# MiniBox.net
KiCad netlist of a schematic drawn in Altium Designer
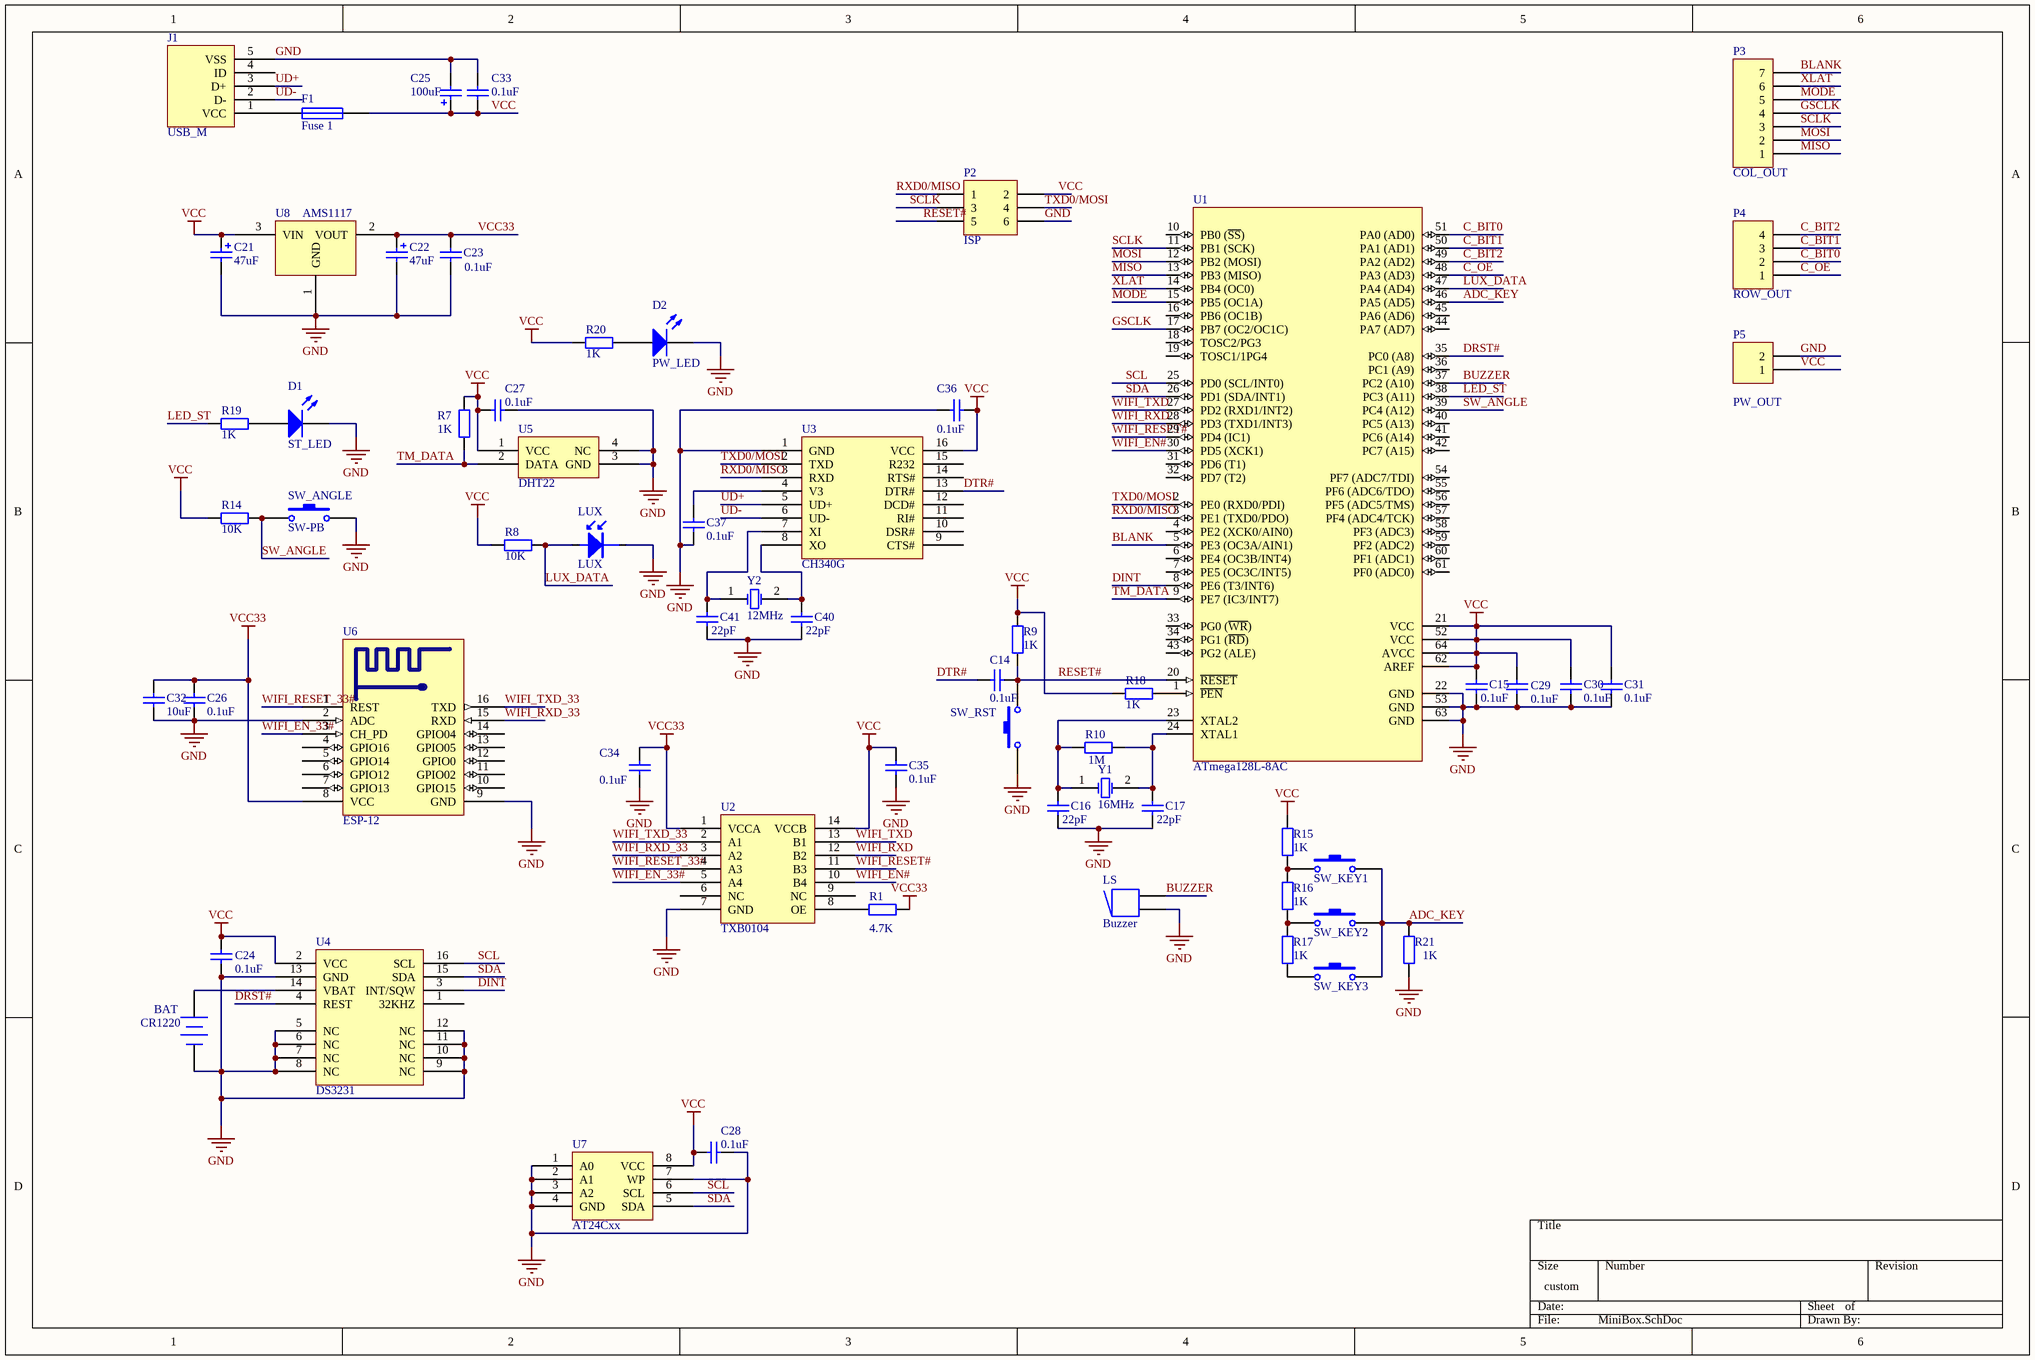
[diagram p0: MiniBox.SchDoc]

(export (version "E")
  (design (tool "Eeschema 10.0.6"))
  (components
    (comp (ref "BAT")
      (value "CR1220")
      (footprint "CR1220")
      (description "Multicell Battery")
      (fields (field (name "PUBLISHER") "Altium Limited"))
      (libsource (lib "Miscellaneous Devices") (part "Battery"))
    )
    (comp (ref "C14")
      (value "0.1uF")
      (footprint "C-0805")
      (description "Capacitor")
      (fields (field (name "Comment") "Cap") (field (name "PUBLISHER") "Altium Limited"))
      (libsource (lib "Miscellaneous Devices") (part "Cap"))
    )
    (comp (ref "C15")
      (value "0.1uF")
      (footprint "C-0805")
      (description "Capacitor")
      (fields (field (name "Comment") "Cap") (field (name "PUBLISHER") "Altium Limited"))
      (libsource (lib "Miscellaneous Devices") (part "Cap"))
    )
    (comp (ref "C16")
      (value "22pF")
      (footprint "C-0805")
      (description "Capacitor")
      (fields (field (name "Comment") "Cap") (field (name "PUBLISHER") "Altium Limited"))
      (libsource (lib "Miscellaneous Devices") (part "Cap"))
    )
    (comp (ref "C17")
      (value "22pF")
      (footprint "C-0805")
      (description "Capacitor")
      (fields (field (name "Comment") "Cap") (field (name "PUBLISHER") "Altium Limited"))
      (libsource (lib "Miscellaneous Devices") (part "Cap"))
    )
    (comp (ref "C21")
      (value "47uF")
      (footprint "CAP-3528")
      (description "Polarized Capacitor (Axial)")
      (fields (field (name "Comment") "Cap Pol2") (field (name "PUBLISHER") "Altium Limited"))
      (libsource (lib "Miscellaneous Devices") (part "Cap Pol2"))
    )
    (comp (ref "C22")
      (value "47uF")
      (footprint "CAP-3528")
      (description "Polarized Capacitor (Axial)")
      (fields (field (name "Comment") "Cap Pol2") (field (name "PUBLISHER") "Altium Limited"))
      (libsource (lib "Miscellaneous Devices") (part "Cap Pol2"))
    )
    (comp (ref "C23")
      (value "0.1uF")
      (footprint "C-0805")
      (description "Capacitor")
      (fields (field (name "Comment") "Cap") (field (name "PUBLISHER") "Altium Limited"))
      (libsource (lib "Miscellaneous Devices") (part "Cap"))
    )
    (comp (ref "C24")
      (value "0.1uF")
      (footprint "C-0805")
      (description "Capacitor")
      (fields (field (name "Comment") "Cap") (field (name "PUBLISHER") "Altium Limited"))
      (libsource (lib "Miscellaneous Devices") (part "Cap"))
    )
    (comp (ref "C25")
      (value "100uF")
      (footprint "CAPAE-D")
      (description "Polarized Capacitor (Axial)")
      (fields (field (name "Comment") "Cap Pol2") (field (name "PUBLISHER") "Altium Limited"))
      (libsource (lib "Miscellaneous Devices") (part "Cap Pol2"))
    )
    (comp (ref "C26")
      (value "0.1uF")
      (footprint "C-0805")
      (description "Capacitor")
      (fields (field (name "Comment") "Cap") (field (name "PUBLISHER") "Altium Limited"))
      (libsource (lib "Miscellaneous Devices") (part "Cap"))
    )
    (comp (ref "C27")
      (value "0.1uF")
      (footprint "C-0805")
      (description "Capacitor")
      (fields (field (name "Comment") "Cap") (field (name "PUBLISHER") "Altium Limited"))
      (libsource (lib "Miscellaneous Devices") (part "Cap"))
    )
    (comp (ref "C28")
      (value "0.1uF")
      (footprint "C-0805")
      (description "Capacitor")
      (fields (field (name "Comment") "Cap") (field (name "PUBLISHER") "Altium Limited"))
      (libsource (lib "Miscellaneous Devices") (part "Cap"))
    )
    (comp (ref "C29")
      (value "0.1uF")
      (footprint "C-0805")
      (description "Capacitor")
      (fields (field (name "Comment") "Cap") (field (name "PUBLISHER") "Altium Limited"))
      (libsource (lib "Miscellaneous Devices") (part "Cap"))
    )
    (comp (ref "C30")
      (value "0.1uF")
      (footprint "C-0805")
      (description "Capacitor")
      (fields (field (name "Comment") "Cap") (field (name "PUBLISHER") "Altium Limited"))
      (libsource (lib "Miscellaneous Devices") (part "Cap"))
    )
    (comp (ref "C31")
      (value "0.1uF")
      (footprint "C-0805")
      (description "Capacitor")
      (fields (field (name "Comment") "Cap") (field (name "PUBLISHER") "Altium Limited"))
      (libsource (lib "Miscellaneous Devices") (part "Cap"))
    )
    (comp (ref "C32")
      (value "10uF")
      (footprint "C-0805")
      (description "Capacitor")
      (fields (field (name "Comment") "Cap") (field (name "PUBLISHER") "Altium Limited"))
      (libsource (lib "Miscellaneous Devices") (part "Cap"))
    )
    (comp (ref "C33")
      (value "0.1uF")
      (footprint "C-0805")
      (description "Capacitor")
      (fields (field (name "Comment") "Cap") (field (name "PUBLISHER") "Altium Limited"))
      (libsource (lib "Miscellaneous Devices") (part "Cap"))
    )
    (comp (ref "C34")
      (value "0.1uF")
      (footprint "C-0805")
      (description "Capacitor")
      (fields (field (name "Comment") "Cap") (field (name "PUBLISHER") "Altium Limited"))
      (libsource (lib "Miscellaneous Devices") (part "Cap"))
    )
    (comp (ref "C35")
      (value "0.1uF")
      (footprint "C-0805")
      (description "Capacitor")
      (fields (field (name "Comment") "Cap") (field (name "PUBLISHER") "Altium Limited"))
      (libsource (lib "Miscellaneous Devices") (part "Cap"))
    )
    (comp (ref "C36")
      (value "0.1uF")
      (footprint "C-0805")
      (description "Capacitor")
      (fields (field (name "Comment") "Cap") (field (name "PUBLISHER") "Altium Limited"))
      (libsource (lib "Miscellaneous Devices") (part "Cap"))
    )
    (comp (ref "C37")
      (value "0.1uF")
      (footprint "C-0805")
      (description "Capacitor")
      (fields (field (name "Comment") "Cap") (field (name "PUBLISHER") "Altium Limited"))
      (libsource (lib "Miscellaneous Devices") (part "Cap"))
    )
    (comp (ref "C40")
      (value "22pF")
      (footprint "C-0805")
      (description "Capacitor")
      (fields (field (name "Comment") "Cap") (field (name "PUBLISHER") "Altium Limited"))
      (libsource (lib "Miscellaneous Devices") (part "Cap"))
    )
    (comp (ref "C41")
      (value "22pF")
      (footprint "C-0805")
      (description "Capacitor")
      (fields (field (name "Comment") "Cap") (field (name "PUBLISHER") "Altium Limited"))
      (libsource (lib "Miscellaneous Devices") (part "Cap"))
    )
    (comp (ref "D1")
      (value "ST_LED")
      (footprint "LED-0805")
      (description "Typical RED, GREEN, YELLOW, AMBER GaAs LED")
      (fields (field (name "PUBLISHER") "Altium Limited"))
      (libsource (lib "Miscellaneous Devices") (part "LED2"))
    )
    (comp (ref "D2")
      (value "PW_LED")
      (footprint "LED-0805")
      (description "Typical RED, GREEN, YELLOW, AMBER GaAs LED")
      (fields (field (name "PUBLISHER") "Altium Limited"))
      (libsource (lib "Miscellaneous Devices") (part "LED2"))
    )
    (comp (ref "F1")
      (value "Fuse 1")
      (footprint "0805-1")
      (description "Fuse")
      (fields (field (name "PUBLISHER") "Altium Limited"))
      (libsource (lib "Miscellaneous Devices") (part "Fuse 1"))
    )
    (comp (ref "J1")
      (value "USB_M")
      (footprint "USB_MICRO_5S_B")
      (description "Micro/Mini USB")
      (libsource (lib "HDR_Fszhang") (part "USB_M"))
    )
    (comp (ref "LS")
      (value "Buzzer")
      (footprint "BEEP-S")
      (description "Magnetic Transducer Buzzer")
      (fields (field (name "PUBLISHER") "Altium Limited"))
      (libsource (lib "Miscellaneous Devices") (part "Buzzer"))
    )
    (comp (ref "LUX") (value "LUX") (libsource (lib "Schlib1") (part "LUX")))
    (comp (ref "P2")
      (value "ISP")
      (footprint "HDR2X3")
      (description "Header, 3-Pin, Dual row")
      (fields (field (name "PUBLISHER") "Altium Limited"))
      (libsource (lib "Miscellaneous Connectors") (part "Header 3X2"))
    )
    (comp (ref "P3")
      (value "COL_OUT")
      (footprint "HDR1X7")
      (description "Header, 7-Pin")
      (fields (field (name "PUBLISHER") "Altium Limited"))
      (libsource (lib "Miscellaneous Connectors") (part "Header 7"))
    )
    (comp (ref "P4")
      (value "ROW_OUT")
      (footprint "HDR1X4")
      (description "Header, 4-Pin")
      (fields (field (name "PUBLISHER") "Altium Limited"))
      (libsource (lib "Miscellaneous Connectors") (part "Header 4"))
    )
    (comp (ref "P5")
      (value "PW_OUT")
      (footprint "HDR1X2")
      (description "Header, 2-Pin")
      (fields (field (name "PUBLISHER") "Altium Limited"))
      (libsource (lib "Miscellaneous Connectors") (part "Header 2"))
    )
    (comp (ref "R1")
      (value "4.7K")
      (footprint "0805-1")
      (description "Resistor")
      (fields (field (name "Comment") "Res2") (field (name "PUBLISHER") "Altium Limited"))
      (libsource (lib "") (part "Res2_1"))
    )
    (comp (ref "R7")
      (value "1K")
      (footprint "0805-1")
      (description "Resistor")
      (fields (field (name "Comment") "Res2") (field (name "PUBLISHER") "Altium Limited"))
      (libsource (lib "Miscellaneous Devices") (part "Res2"))
    )
    (comp (ref "R8")
      (value "10K")
      (footprint "0805-1")
      (description "Resistor")
      (fields (field (name "Comment") "Res2") (field (name "PUBLISHER") "Altium Limited"))
      (libsource (lib "") (part "Res2_2"))
    )
    (comp (ref "R9")
      (value "1K")
      (footprint "0805-1")
      (description "Resistor")
      (fields (field (name "Comment") "Res2") (field (name "PUBLISHER") "Altium Limited"))
      (libsource (lib "Miscellaneous Devices") (part "Res2"))
    )
    (comp (ref "R10")
      (value "1M")
      (footprint "0805-1")
      (description "Resistor")
      (fields (field (name "Comment") "Res2") (field (name "PUBLISHER") "Altium Limited"))
      (libsource (lib "") (part "Res2_1"))
    )
    (comp (ref "R14")
      (value "10K")
      (footprint "0805-1")
      (description "Resistor")
      (fields (field (name "Comment") "Res2") (field (name "PUBLISHER") "Altium Limited"))
      (libsource (lib "") (part "Res2_2"))
    )
    (comp (ref "R15")
      (value "1K")
      (footprint "0805-1")
      (description "Resistor")
      (fields (field (name "Comment") "Res2") (field (name "PUBLISHER") "Altium Limited"))
      (libsource (lib "Miscellaneous Devices") (part "Res2"))
    )
    (comp (ref "R16")
      (value "1K")
      (footprint "0805-1")
      (description "Resistor")
      (fields (field (name "Comment") "Res2") (field (name "PUBLISHER") "Altium Limited"))
      (libsource (lib "Miscellaneous Devices") (part "Res2"))
    )
    (comp (ref "R17")
      (value "1K")
      (footprint "0805-1")
      (description "Resistor")
      (fields (field (name "Comment") "Res2") (field (name "PUBLISHER") "Altium Limited"))
      (libsource (lib "Miscellaneous Devices") (part "Res2"))
    )
    (comp (ref "R18")
      (value "1K")
      (footprint "0805-1")
      (description "Resistor")
      (fields (field (name "Comment") "Res2") (field (name "PUBLISHER") "Altium Limited"))
      (libsource (lib "") (part "Res2_2"))
    )
    (comp (ref "R19")
      (value "1K")
      (footprint "0805-1")
      (description "Resistor")
      (fields (field (name "Comment") "Res2") (field (name "PUBLISHER") "Altium Limited"))
      (libsource (lib "") (part "Res2_2"))
    )
    (comp (ref "R20")
      (value "1K")
      (footprint "0805-1")
      (description "Resistor")
      (fields (field (name "Comment") "Res2") (field (name "PUBLISHER") "Altium Limited"))
      (libsource (lib "") (part "Res2_2"))
    )
    (comp (ref "R21")
      (value "1K")
      (footprint "0805-1")
      (description "Resistor")
      (fields (field (name "Comment") "Res2") (field (name "PUBLISHER") "Altium Limited"))
      (libsource (lib "") (part "Res2_3"))
    )
    (comp (ref "SW_ANGLE")
      (value "SW-PB")
      (footprint "AX_2.54")
      (description "Switch")
      (fields (field (name "PUBLISHER") "Altium Limited"))
      (libsource (lib "Miscellaneous Devices") (part "SW-PB"))
    )
    (comp (ref "SW_KEY1")
      (value "SW-PB")
      (footprint "SW_B")
      (description "Switch")
      (fields (field (name "PUBLISHER") "Altium Limited"))
      (libsource (lib "Miscellaneous Devices") (part "SW-PB"))
    )
    (comp (ref "SW_KEY2")
      (value "SW-PB")
      (footprint "SW_B")
      (description "Switch")
      (fields (field (name "PUBLISHER") "Altium Limited"))
      (libsource (lib "Miscellaneous Devices") (part "SW-PB"))
    )
    (comp (ref "SW_KEY3")
      (value "SW-PB")
      (footprint "SW_B")
      (description "Switch")
      (fields (field (name "PUBLISHER") "Altium Limited"))
      (libsource (lib "Miscellaneous Devices") (part "SW-PB"))
    )
    (comp (ref "SW_RST")
      (value "SW-PB")
      (footprint "SW_B")
      (description "Switch")
      (fields (field (name "PUBLISHER") "Altium Limited"))
      (libsource (lib "Miscellaneous Devices") (part "SW-PB"))
    )
    (comp (ref "U1")
      (value "ATmega128L-8AC")
      (footprint "64A_N")
      (description "8-Bit AVR Microcontroller with 128K Bytes of In-System Programmable Flash Memory")
      (fields (field (name "PUBLISHER") "Altium Limited"))
      (libsource (lib "Atmel Microcontroller 8-Bit AVR") (part "ATmega128L-8AC"))
    )
    (comp (ref "U2") (value "TXB0104") (footprint "TSSOP-14") (libsource (lib "Schlib1") (part "TXB0104")))
    (comp (ref "U3") (value "CH340G") (footprint "SOIC-16") (libsource (lib "Schlib1") (part "CH340G")))
    (comp (ref "U4") (value "DS3231") (footprint "SOIC-16W") (libsource (lib "Schlib1") (part "DS3231")))
    (comp (ref "U5") (value "DHT22") (footprint "DHTxx") (libsource (lib "Schlib1") (part "DHT22")))
    (comp (ref "U6") (value "ESP-12") (footprint "ESP_12") (libsource (lib "ESP-12") (part "ESP-12")))
    (comp (ref "U7") (value "AT24Cxx") (footprint "SOIC-8") (libsource (lib "Schlib1") (part "AT24Cxx")))
    (comp (ref "U8") (value "AMS1117") (footprint "SOT223") (libsource (lib "Schlib1") (part "AMS1117")))
    (comp (ref "Y1")
      (value "16MHz")
      (footprint "X-SM49")
      (description "Crystal Oscillator")
      (fields (field (name "PUBLISHER") "Altium Limited"))
      (libsource (lib "Miscellaneous Devices") (part "XTAL"))
    )
    (comp (ref "Y2")
      (value "12MHz")
      (footprint "X-SM49")
      (description "Crystal Oscillator")
      (fields (field (name "PUBLISHER") "Altium Limited"))
      (libsource (lib "Miscellaneous Devices") (part "XTAL"))
    )
  )
  (nets
    (net (code "1") (name "/ADC_KEY") (class "Default")
      (node (ref "R21") (pin "1") (pinfunction "1_1") (pintype "passive"))
      (node (ref "SW_KEY1") (pin "2") (pinfunction "2_2") (pintype "passive"))
      (node (ref "SW_KEY2") (pin "2") (pinfunction "2_2") (pintype "passive"))
      (node (ref "SW_KEY3") (pin "2") (pinfunction "2_2") (pintype "passive"))
      (node (ref "U1") (pin "46") (pinfunction "PA5_(AD5)_46") (pintype "bidirectional"))
    )
    (net (code "2") (name "/BLANK") (class "Default")
      (node (ref "P3") (pin "7") (pinfunction "7_7") (pintype "passive"))
      (node (ref "U1") (pin "5") (pinfunction "PE3_(OC3A/AIN1)_5") (pintype "bidirectional"))
    )
    (net (code "3") (name "/BUZZER") (class "Default")
      (node (ref "LS") (pin "2") (pinfunction "2_2") (pintype "passive"))
      (node (ref "U1") (pin "37") (pinfunction "PC2_(A10)_37") (pintype "bidirectional"))
    )
    (net (code "4") (name "/C_BIT0") (class "Default")
      (node (ref "P4") (pin "2") (pinfunction "2_2") (pintype "passive"))
      (node (ref "U1") (pin "51") (pinfunction "PA0_(AD0)_51") (pintype "bidirectional"))
    )
    (net (code "5") (name "/C_BIT1") (class "Default")
      (node (ref "P4") (pin "3") (pinfunction "3_3") (pintype "passive"))
      (node (ref "U1") (pin "50") (pinfunction "PA1_(AD1)_50") (pintype "bidirectional"))
    )
    (net (code "6") (name "/C_BIT2") (class "Default")
      (node (ref "P4") (pin "4") (pinfunction "4_4") (pintype "passive"))
      (node (ref "U1") (pin "49") (pinfunction "PA2_(AD2)_49") (pintype "bidirectional"))
    )
    (net (code "7") (name "/C_OE") (class "Default")
      (node (ref "P4") (pin "1") (pinfunction "1_1") (pintype "passive"))
      (node (ref "U1") (pin "48") (pinfunction "PA3_(AD3)_48") (pintype "bidirectional"))
    )
    (net (code "8") (name "/DINT") (class "Default")
      (node (ref "U1") (pin "8") (pinfunction "PE6_(T3/INT6)_8") (pintype "bidirectional"))
      (node (ref "U4") (pin "3") (pinfunction "INT/SQW_3") (pintype "passive"))
    )
    (net (code "9") (name "/DRST#") (class "Default")
      (node (ref "U1") (pin "35") (pinfunction "PC0_(A8)_35") (pintype "bidirectional"))
      (node (ref "U4") (pin "4") (pinfunction "REST_4") (pintype "passive"))
    )
    (net (code "10") (name "/DTR#") (class "Default")
      (node (ref "C14") (pin "1") (pinfunction "1_1") (pintype "passive"))
      (node (ref "U3") (pin "13") (pinfunction "DTR#_13") (pintype "passive"))
    )
    (net (code "11") (name "/GSCLK") (class "Default")
      (node (ref "P3") (pin "4") (pinfunction "4_4") (pintype "passive"))
      (node (ref "U1") (pin "17") (pinfunction "PB7_(OC2/OC1C)_17") (pintype "bidirectional"))
    )
    (net (code "12") (name "/LED_ST") (class "Default")
      (node (ref "R19") (pin "2") (pinfunction "2_2") (pintype "passive"))
      (node (ref "U1") (pin "38") (pinfunction "PC3_(A11)_38") (pintype "bidirectional"))
    )
    (net (code "13") (name "/LUX_DATA") (class "Default")
      (node (ref "LUX") (pin "1") (pinfunction "1_1") (pintype "passive"))
      (node (ref "R8") (pin "1") (pinfunction "1_1") (pintype "passive"))
      (node (ref "U1") (pin "47") (pinfunction "PA4_(AD4)_47") (pintype "bidirectional"))
    )
    (net (code "14") (name "/MISO") (class "Default")
      (node (ref "P3") (pin "1") (pinfunction "1_1") (pintype "passive"))
      (node (ref "U1") (pin "13") (pinfunction "PB3_(MISO)_13") (pintype "bidirectional"))
    )
    (net (code "15") (name "/MODE") (class "Default")
      (node (ref "P3") (pin "5") (pinfunction "5_5") (pintype "passive"))
      (node (ref "U1") (pin "15") (pinfunction "PB5_(OC1A)_15") (pintype "bidirectional"))
    )
    (net (code "16") (name "/MOSI") (class "Default")
      (node (ref "P3") (pin "2") (pinfunction "2_2") (pintype "passive"))
      (node (ref "U1") (pin "12") (pinfunction "PB2_(MOSI)_12") (pintype "bidirectional"))
    )
    (net (code "17") (name "/RESET#") (class "Default")
      (node (ref "C14") (pin "2") (pinfunction "2_2") (pintype "passive"))
      (node (ref "P2") (pin "5") (pinfunction "5_5") (pintype "passive"))
      (node (ref "R9") (pin "1") (pinfunction "1_1") (pintype "passive"))
      (node (ref "SW_RST") (pin "2") (pinfunction "2_2") (pintype "passive"))
      (node (ref "U1") (pin "20") (pinfunction "~{RESET}_20") (pintype "input"))
    )
    (net (code "18") (name "/RXD0{slash}MISO") (class "Default")
      (node (ref "P2") (pin "1") (pinfunction "1_1") (pintype "passive"))
      (node (ref "U1") (pin "3") (pinfunction "PE1_(TXD0/PDO)_3") (pintype "bidirectional"))
      (node (ref "U3") (pin "3") (pinfunction "RXD_3") (pintype "passive"))
    )
    (net (code "19") (name "/SCL") (class "Default")
      (node (ref "U1") (pin "25") (pinfunction "PD0_(SCL/INT0)_25") (pintype "bidirectional"))
      (node (ref "U4") (pin "16") (pinfunction "SCL_16") (pintype "passive"))
      (node (ref "U7") (pin "6") (pinfunction "SCL_6") (pintype "passive"))
    )
    (net (code "20") (name "/SCLK") (class "Default")
      (node (ref "P2") (pin "3") (pinfunction "3_3") (pintype "passive"))
      (node (ref "P3") (pin "3") (pinfunction "3_3") (pintype "passive"))
      (node (ref "U1") (pin "11") (pinfunction "PB1_(SCK)_11") (pintype "bidirectional"))
    )
    (net (code "21") (name "/SDA") (class "Default")
      (node (ref "U1") (pin "26") (pinfunction "PD1_(SDA/INT1)_26") (pintype "bidirectional"))
      (node (ref "U4") (pin "15") (pinfunction "SDA_15") (pintype "passive"))
      (node (ref "U7") (pin "5") (pinfunction "SDA_5") (pintype "passive"))
    )
    (net (code "22") (name "/SW_ANGLE") (class "Default")
      (node (ref "R14") (pin "1") (pinfunction "1_1") (pintype "passive"))
      (node (ref "SW_ANGLE") (pin "1") (pinfunction "1_1") (pintype "passive"))
      (node (ref "U1") (pin "39") (pinfunction "PC4_(A12)_39") (pintype "bidirectional"))
    )
    (net (code "23") (name "/TM_DATA") (class "Default")
      (node (ref "R7") (pin "1") (pinfunction "1_1") (pintype "passive"))
      (node (ref "U1") (pin "9") (pinfunction "PE7_(IC3/INT7)_9") (pintype "bidirectional"))
      (node (ref "U5") (pin "2") (pinfunction "DATA_2") (pintype "passive"))
    )
    (net (code "24") (name "/TXD0{slash}MOSI") (class "Default")
      (node (ref "P2") (pin "4") (pinfunction "4_4") (pintype "passive"))
      (node (ref "U1") (pin "2") (pinfunction "PE0_(RXD0/PDI)_2") (pintype "bidirectional"))
      (node (ref "U3") (pin "2") (pinfunction "TXD_2") (pintype "passive"))
    )
    (net (code "25") (name "/UD+") (class "Default")
      (node (ref "J1") (pin "3") (pinfunction "D+_3") (pintype "passive"))
      (node (ref "U3") (pin "5") (pinfunction "UD+_5") (pintype "passive"))
    )
    (net (code "26") (name "/UD-") (class "Default")
      (node (ref "J1") (pin "2") (pinfunction "D-_2") (pintype "passive"))
      (node (ref "U3") (pin "6") (pinfunction "UD-_6") (pintype "passive"))
    )
    (net (code "27") (name "/WIFI_EN#") (class "Default")
      (node (ref "U1") (pin "30") (pinfunction "PD5_(XCK1)_30") (pintype "bidirectional"))
      (node (ref "U2") (pin "10") (pinfunction "B4_10") (pintype "passive"))
    )
    (net (code "28") (name "/WIFI_EN_33#") (class "Default")
      (node (ref "U2") (pin "5") (pinfunction "A4_5") (pintype "passive"))
      (node (ref "U6") (pin "3") (pinfunction "CH_PD_3") (pintype "input"))
    )
    (net (code "29") (name "/WIFI_RESET#") (class "Default")
      (node (ref "U1") (pin "29") (pinfunction "PD4_(IC1)_29") (pintype "bidirectional"))
      (node (ref "U2") (pin "11") (pinfunction "B3_11") (pintype "passive"))
    )
    (net (code "30") (name "/WIFI_RESET_33#") (class "Default")
      (node (ref "U2") (pin "4") (pinfunction "A3_4") (pintype "passive"))
      (node (ref "U6") (pin "1") (pinfunction "REST_1") (pintype "passive"))
    )
    (net (code "31") (name "/WIFI_RXD") (class "Default")
      (node (ref "U1") (pin "28") (pinfunction "PD3_(TXD1/INT3)_28") (pintype "bidirectional"))
      (node (ref "U2") (pin "12") (pinfunction "B2_12") (pintype "passive"))
    )
    (net (code "32") (name "/WIFI_RXD_33") (class "Default")
      (node (ref "U2") (pin "3") (pinfunction "A2_3") (pintype "passive"))
      (node (ref "U6") (pin "15") (pinfunction "RXD_15") (pintype "input"))
    )
    (net (code "33") (name "/WIFI_TXD") (class "Default")
      (node (ref "U1") (pin "27") (pinfunction "PD2_(RXD1/INT2)_27") (pintype "bidirectional"))
      (node (ref "U2") (pin "13") (pinfunction "B1_13") (pintype "passive"))
    )
    (net (code "34") (name "/WIFI_TXD_33") (class "Default")
      (node (ref "U2") (pin "2") (pinfunction "A1_2") (pintype "passive"))
      (node (ref "U6") (pin "16") (pinfunction "TXD_16") (pintype "output"))
    )
    (net (code "35") (name "/XLAT") (class "Default")
      (node (ref "P3") (pin "6") (pinfunction "6_6") (pintype "passive"))
      (node (ref "U1") (pin "14") (pinfunction "PB4_(OC0)_14") (pintype "bidirectional"))
    )
    (net (code "36") (name "GND") (class "Default")
      (node (ref "BAT") (pin "2") (pinfunction "-_2") (pintype "passive"))
      (node (ref "C15") (pin "1") (pinfunction "1_1") (pintype "passive"))
      (node (ref "C16") (pin "1") (pinfunction "1_1") (pintype "passive"))
      (node (ref "C17") (pin "1") (pinfunction "1_1") (pintype "passive"))
      (node (ref "C21") (pin "2") (pinfunction "2_2") (pintype "passive"))
      (node (ref "C22") (pin "2") (pinfunction "2_2") (pintype "passive"))
      (node (ref "C23") (pin "1") (pinfunction "1_1") (pintype "passive"))
      (node (ref "C24") (pin "1") (pinfunction "1_1") (pintype "passive"))
      (node (ref "C25") (pin "2") (pinfunction "2_2") (pintype "passive"))
      (node (ref "C26") (pin "1") (pinfunction "1_1") (pintype "passive"))
      (node (ref "C27") (pin "1") (pinfunction "1_1") (pintype "passive"))
      (node (ref "C28") (pin "1") (pinfunction "1_1") (pintype "passive"))
      (node (ref "C29") (pin "2") (pinfunction "2_2") (pintype "passive"))
      (node (ref "C30") (pin "2") (pinfunction "2_2") (pintype "passive"))
      (node (ref "C31") (pin "2") (pinfunction "2_2") (pintype "passive"))
      (node (ref "C32") (pin "1") (pinfunction "1_1") (pintype "passive"))
      (node (ref "C33") (pin "2") (pinfunction "2_2") (pintype "passive"))
      (node (ref "C34") (pin "2") (pinfunction "2_2") (pintype "passive"))
      (node (ref "C35") (pin "2") (pinfunction "2_2") (pintype "passive"))
      (node (ref "C36") (pin "1") (pinfunction "1_1") (pintype "passive"))
      (node (ref "C37") (pin "1") (pinfunction "1_1") (pintype "passive"))
      (node (ref "C40") (pin "1") (pinfunction "1_1") (pintype "passive"))
      (node (ref "C41") (pin "1") (pinfunction "1_1") (pintype "passive"))
      (node (ref "D1") (pin "2") (pinfunction "K_2") (pintype "passive"))
      (node (ref "D2") (pin "2") (pinfunction "K_2") (pintype "passive"))
      (node (ref "J1") (pin "5") (pinfunction "VSS_5") (pintype "passive"))
      (node (ref "LS") (pin "1") (pinfunction "1_1") (pintype "passive"))
      (node (ref "LUX") (pin "2") (pinfunction "2_2") (pintype "passive"))
      (node (ref "P2") (pin "6") (pinfunction "6_6") (pintype "passive"))
      (node (ref "P5") (pin "2") (pinfunction "2_2") (pintype "passive"))
      (node (ref "R21") (pin "2") (pinfunction "2_2") (pintype "passive"))
      (node (ref "SW_ANGLE") (pin "2") (pinfunction "2_2") (pintype "passive"))
      (node (ref "SW_RST") (pin "1") (pinfunction "1_1") (pintype "passive"))
      (node (ref "U1") (pin "22") (pinfunction "GND_22") (pintype "power_in"))
      (node (ref "U1") (pin "53") (pinfunction "GND_53") (pintype "power_in"))
      (node (ref "U1") (pin "63") (pinfunction "GND_63") (pintype "power_in"))
      (node (ref "U2") (pin "7") (pinfunction "GND_7") (pintype "passive"))
      (node (ref "U3") (pin "1") (pinfunction "GND_1") (pintype "passive"))
      (node (ref "U4") (pin "10") (pinfunction "NC_10") (pintype "passive"))
      (node (ref "U4") (pin "11") (pinfunction "NC_11") (pintype "passive"))
      (node (ref "U4") (pin "12") (pinfunction "NC_12") (pintype "passive"))
      (node (ref "U4") (pin "13") (pinfunction "GND_13") (pintype "passive"))
      (node (ref "U4") (pin "5") (pinfunction "NC_5") (pintype "passive"))
      (node (ref "U4") (pin "6") (pinfunction "NC_6") (pintype "passive"))
      (node (ref "U4") (pin "7") (pinfunction "NC_7") (pintype "passive"))
      (node (ref "U4") (pin "8") (pinfunction "NC_8") (pintype "passive"))
      (node (ref "U4") (pin "9") (pinfunction "NC_9") (pintype "passive"))
      (node (ref "U5") (pin "3") (pinfunction "GND_3") (pintype "passive"))
      (node (ref "U5") (pin "4") (pinfunction "NC_4") (pintype "passive"))
      (node (ref "U6") (pin "2") (pinfunction "ADC_2") (pintype "input"))
      (node (ref "U6") (pin "9") (pinfunction "GND_9") (pintype "power_in"))
      (node (ref "U7") (pin "1") (pinfunction "A0_1") (pintype "passive"))
      (node (ref "U7") (pin "2") (pinfunction "A1_2") (pintype "passive"))
      (node (ref "U7") (pin "3") (pinfunction "A2_3") (pintype "passive"))
      (node (ref "U7") (pin "4") (pinfunction "GND_4") (pintype "passive"))
      (node (ref "U7") (pin "7") (pinfunction "WP_7") (pintype "passive"))
      (node (ref "U8") (pin "1") (pinfunction "GND_1") (pintype "passive"))
    )
    (net (code "37") (name "Net-(BAT-+)") (class "Default")
      (node (ref "BAT") (pin "1") (pinfunction "+_1") (pintype "passive"))
      (node (ref "U4") (pin "14") (pinfunction "VBAT_14") (pintype "passive"))
    )
    (net (code "38") (name "Net-(D1-A)") (class "Default")
      (node (ref "D1") (pin "1") (pinfunction "A_1") (pintype "passive"))
      (node (ref "R19") (pin "1") (pinfunction "1_1") (pintype "passive"))
    )
    (net (code "39") (name "Net-(D2-A)") (class "Default")
      (node (ref "D2") (pin "1") (pinfunction "A_1") (pintype "passive"))
      (node (ref "R20") (pin "1") (pinfunction "1_1") (pintype "passive"))
    )
    (net (code "40") (name "Net-(J1-VCC)") (class "Default")
      (node (ref "F1") (pin "1") (pinfunction "1_1") (pintype "passive"))
      (node (ref "J1") (pin "1") (pinfunction "VCC_1") (pintype "passive"))
    )
    (net (code "41") (name "Net-(R15-Pad1)") (class "Default")
      (node (ref "R15") (pin "1") (pinfunction "1_1") (pintype "passive"))
      (node (ref "R16") (pin "2") (pinfunction "2_2") (pintype "passive"))
      (node (ref "SW_KEY1") (pin "1") (pinfunction "1_1") (pintype "passive"))
    )
    (net (code "42") (name "Net-(R16-Pad1)") (class "Default")
      (node (ref "R16") (pin "1") (pinfunction "1_1") (pintype "passive"))
      (node (ref "R17") (pin "2") (pinfunction "2_2") (pintype "passive"))
      (node (ref "SW_KEY2") (pin "1") (pinfunction "1_1") (pintype "passive"))
    )
    (net (code "43") (name "Net-(R17-Pad1)") (class "Default")
      (node (ref "R17") (pin "1") (pinfunction "1_1") (pintype "passive"))
      (node (ref "SW_KEY3") (pin "1") (pinfunction "1_1") (pintype "passive"))
    )
    (net (code "44") (name "Net-(U1-XTAL1)") (class "Default")
      (node (ref "C17") (pin "2") (pinfunction "2_2") (pintype "passive"))
      (node (ref "R10") (pin "2") (pinfunction "2_2") (pintype "passive"))
      (node (ref "U1") (pin "24") (pinfunction "XTAL1_24") (pintype "passive"))
      (node (ref "Y1") (pin "2") (pinfunction "OSC2_2") (pintype "passive"))
    )
    (net (code "45") (name "Net-(U1-XTAL2)") (class "Default")
      (node (ref "C16") (pin "2") (pinfunction "2_2") (pintype "passive"))
      (node (ref "R10") (pin "1") (pinfunction "1_1") (pintype "passive"))
      (node (ref "U1") (pin "23") (pinfunction "XTAL2_23") (pintype "passive"))
      (node (ref "Y1") (pin "1") (pinfunction "OSC1_1") (pintype "passive"))
    )
    (net (code "46") (name "Net-(U1-~{PEN})") (class "Default")
      (node (ref "R18") (pin "1") (pinfunction "1_1") (pintype "passive"))
      (node (ref "U1") (pin "1") (pinfunction "~{PEN}_1") (pintype "input"))
    )
    (net (code "47") (name "Net-(U2-OE)") (class "Default")
      (node (ref "R1") (pin "1") (pinfunction "1_1") (pintype "passive"))
      (node (ref "U2") (pin "8") (pinfunction "OE_8") (pintype "passive"))
    )
    (net (code "48") (name "Net-(U3-V3)") (class "Default")
      (node (ref "C37") (pin "2") (pinfunction "2_2") (pintype "passive"))
      (node (ref "U3") (pin "4") (pinfunction "V3_4") (pintype "passive"))
    )
    (net (code "49") (name "Net-(U3-XI)") (class "Default")
      (node (ref "C41") (pin "2") (pinfunction "2_2") (pintype "passive"))
      (node (ref "U3") (pin "7") (pinfunction "XI_7") (pintype "passive"))
      (node (ref "Y2") (pin "1") (pinfunction "OSC1_1") (pintype "passive"))
    )
    (net (code "50") (name "Net-(U3-XO)") (class "Default")
      (node (ref "C40") (pin "2") (pinfunction "2_2") (pintype "passive"))
      (node (ref "U3") (pin "8") (pinfunction "XO_8") (pintype "passive"))
      (node (ref "Y2") (pin "2") (pinfunction "OSC2_2") (pintype "passive"))
    )
    (net (code "51") (name "VCC") (class "Default")
      (node (ref "C15") (pin "2") (pinfunction "2_2") (pintype "passive"))
      (node (ref "C21") (pin "1") (pinfunction "1_1") (pintype "passive"))
      (node (ref "C24") (pin "2") (pinfunction "2_2") (pintype "passive"))
      (node (ref "C25") (pin "1") (pinfunction "1_1") (pintype "passive"))
      (node (ref "C27") (pin "2") (pinfunction "2_2") (pintype "passive"))
      (node (ref "C28") (pin "2") (pinfunction "2_2") (pintype "passive"))
      (node (ref "C29") (pin "1") (pinfunction "1_1") (pintype "passive"))
      (node (ref "C30") (pin "1") (pinfunction "1_1") (pintype "passive"))
      (node (ref "C31") (pin "1") (pinfunction "1_1") (pintype "passive"))
      (node (ref "C33") (pin "1") (pinfunction "1_1") (pintype "passive"))
      (node (ref "C35") (pin "1") (pinfunction "1_1") (pintype "passive"))
      (node (ref "C36") (pin "2") (pinfunction "2_2") (pintype "passive"))
      (node (ref "F1") (pin "2") (pinfunction "2_2") (pintype "passive"))
      (node (ref "P2") (pin "2") (pinfunction "2_2") (pintype "passive"))
      (node (ref "P5") (pin "1") (pinfunction "1_1") (pintype "passive"))
      (node (ref "R14") (pin "2") (pinfunction "2_2") (pintype "passive"))
      (node (ref "R15") (pin "2") (pinfunction "2_2") (pintype "passive"))
      (node (ref "R18") (pin "2") (pinfunction "2_2") (pintype "passive"))
      (node (ref "R20") (pin "2") (pinfunction "2_2") (pintype "passive"))
      (node (ref "R7") (pin "2") (pinfunction "2_2") (pintype "passive"))
      (node (ref "R8") (pin "2") (pinfunction "2_2") (pintype "passive"))
      (node (ref "R9") (pin "2") (pinfunction "2_2") (pintype "passive"))
      (node (ref "U1") (pin "21") (pinfunction "VCC_21") (pintype "power_in"))
      (node (ref "U1") (pin "52") (pinfunction "VCC_52") (pintype "power_in"))
      (node (ref "U1") (pin "62") (pinfunction "AREF_62") (pintype "passive"))
      (node (ref "U1") (pin "64") (pinfunction "AVCC_64") (pintype "power_in"))
      (node (ref "U2") (pin "14") (pinfunction "VCCB_14") (pintype "passive"))
      (node (ref "U3") (pin "16") (pinfunction "VCC_16") (pintype "passive"))
      (node (ref "U4") (pin "2") (pinfunction "VCC_2") (pintype "passive"))
      (node (ref "U5") (pin "1") (pinfunction "VCC_1") (pintype "passive"))
      (node (ref "U7") (pin "8") (pinfunction "VCC_8") (pintype "passive"))
      (node (ref "U8") (pin "3") (pinfunction "VIN_3") (pintype "passive"))
    )
    (net (code "52") (name "VCC33") (class "Default")
      (node (ref "C22") (pin "1") (pinfunction "1_1") (pintype "passive"))
      (node (ref "C23") (pin "2") (pinfunction "2_2") (pintype "passive"))
      (node (ref "C26") (pin "2") (pinfunction "2_2") (pintype "passive"))
      (node (ref "C32") (pin "2") (pinfunction "2_2") (pintype "passive"))
      (node (ref "C34") (pin "1") (pinfunction "1_1") (pintype "passive"))
      (node (ref "R1") (pin "2") (pinfunction "2_2") (pintype "passive"))
      (node (ref "U2") (pin "1") (pinfunction "VCCA_1") (pintype "passive"))
      (node (ref "U6") (pin "8") (pinfunction "VCC_8") (pintype "power_in"))
      (node (ref "U8") (pin "2") (pinfunction "VOUT_2") (pintype "passive"))
    )
    (net (code "53") (name "unconnected-(J1-ID-Pad4)") (class "Default")
      (node (ref "J1") (pin "4") (pinfunction "ID_4") (pintype "passive"))
    )
    (net (code "54") (name "unconnected-(U1-PA6_(AD6)-Pad45)") (class "Default")
      (node (ref "U1") (pin "45") (pinfunction "PA6_(AD6)_45") (pintype "bidirectional"))
    )
    (net (code "55") (name "unconnected-(U1-PA7_(AD7)-Pad44)") (class "Default")
      (node (ref "U1") (pin "44") (pinfunction "PA7_(AD7)_44") (pintype "bidirectional"))
    )
    (net (code "56") (name "unconnected-(U1-PB0_(~{SS})-Pad10)") (class "Default")
      (node (ref "U1") (pin "10") (pinfunction "PB0_(~{SS})_10") (pintype "bidirectional"))
    )
    (net (code "57") (name "unconnected-(U1-PB6_(OC1B)-Pad16)") (class "Default")
      (node (ref "U1") (pin "16") (pinfunction "PB6_(OC1B)_16") (pintype "bidirectional"))
    )
    (net (code "58") (name "unconnected-(U1-PC1_(A9)-Pad36)") (class "Default")
      (node (ref "U1") (pin "36") (pinfunction "PC1_(A9)_36") (pintype "bidirectional"))
    )
    (net (code "59") (name "unconnected-(U1-PC5_(A13)-Pad40)") (class "Default")
      (node (ref "U1") (pin "40") (pinfunction "PC5_(A13)_40") (pintype "bidirectional"))
    )
    (net (code "60") (name "unconnected-(U1-PC6_(A14)-Pad41)") (class "Default")
      (node (ref "U1") (pin "41") (pinfunction "PC6_(A14)_41") (pintype "bidirectional"))
    )
    (net (code "61") (name "unconnected-(U1-PC7_(A15)-Pad42)") (class "Default")
      (node (ref "U1") (pin "42") (pinfunction "PC7_(A15)_42") (pintype "bidirectional"))
    )
    (net (code "62") (name "unconnected-(U1-PD6_(T1)-Pad31)") (class "Default")
      (node (ref "U1") (pin "31") (pinfunction "PD6_(T1)_31") (pintype "bidirectional"))
    )
    (net (code "63") (name "unconnected-(U1-PD7_(T2)-Pad32)") (class "Default")
      (node (ref "U1") (pin "32") (pinfunction "PD7_(T2)_32") (pintype "bidirectional"))
    )
    (net (code "64") (name "unconnected-(U1-PE2_(XCK0{slash}AIN0)-Pad4)") (class "Default")
      (node (ref "U1") (pin "4") (pinfunction "PE2_(XCK0/AIN0)_4") (pintype "bidirectional"))
    )
    (net (code "65") (name "unconnected-(U1-PE4_(OC3B{slash}INT4)-Pad6)") (class "Default")
      (node (ref "U1") (pin "6") (pinfunction "PE4_(OC3B/INT4)_6") (pintype "bidirectional"))
    )
    (net (code "66") (name "unconnected-(U1-PE5_(OC3C{slash}INT5)-Pad7)") (class "Default")
      (node (ref "U1") (pin "7") (pinfunction "PE5_(OC3C/INT5)_7") (pintype "bidirectional"))
    )
    (net (code "67") (name "unconnected-(U1-PF0_(ADC0)-Pad61)") (class "Default")
      (node (ref "U1") (pin "61") (pinfunction "PF0_(ADC0)_61") (pintype "bidirectional"))
    )
    (net (code "68") (name "unconnected-(U1-PF1_(ADC1)-Pad60)") (class "Default")
      (node (ref "U1") (pin "60") (pinfunction "PF1_(ADC1)_60") (pintype "bidirectional"))
    )
    (net (code "69") (name "unconnected-(U1-PF2_(ADC2)-Pad59)") (class "Default")
      (node (ref "U1") (pin "59") (pinfunction "PF2_(ADC2)_59") (pintype "bidirectional"))
    )
    (net (code "70") (name "unconnected-(U1-PF3_(ADC3)-Pad58)") (class "Default")
      (node (ref "U1") (pin "58") (pinfunction "PF3_(ADC3)_58") (pintype "bidirectional"))
    )
    (net (code "71") (name "unconnected-(U1-PF4_(ADC4{slash}TCK)-Pad57)") (class "Default")
      (node (ref "U1") (pin "57") (pinfunction "PF4_(ADC4/TCK)_57") (pintype "bidirectional"))
    )
    (net (code "72") (name "unconnected-(U1-PF5_(ADC5{slash}TMS)-Pad56)") (class "Default")
      (node (ref "U1") (pin "56") (pinfunction "PF5_(ADC5/TMS)_56") (pintype "bidirectional"))
    )
    (net (code "73") (name "unconnected-(U1-PF6_(ADC6{slash}TDO)-Pad55)") (class "Default")
      (node (ref "U1") (pin "55") (pinfunction "PF6_(ADC6/TDO)_55") (pintype "bidirectional"))
    )
    (net (code "74") (name "unconnected-(U1-PF7_(ADC7{slash}TDI)-Pad54)") (class "Default")
      (node (ref "U1") (pin "54") (pinfunction "PF7_(ADC7/TDI)_54") (pintype "bidirectional"))
    )
    (net (code "75") (name "unconnected-(U1-PG0_(~{WR})-Pad33)") (class "Default")
      (node (ref "U1") (pin "33") (pinfunction "PG0_(~{WR})_33") (pintype "bidirectional"))
    )
    (net (code "76") (name "unconnected-(U1-PG1_(~{RD})-Pad34)") (class "Default")
      (node (ref "U1") (pin "34") (pinfunction "PG1_(~{RD})_34") (pintype "bidirectional"))
    )
    (net (code "77") (name "unconnected-(U1-PG2_(ALE)-Pad43)") (class "Default")
      (node (ref "U1") (pin "43") (pinfunction "PG2_(ALE)_43") (pintype "bidirectional"))
    )
    (net (code "78") (name "unconnected-(U1-TOSC1{slash}1PG4-Pad19)") (class "Default")
      (node (ref "U1") (pin "19") (pinfunction "TOSC1/1PG4_19") (pintype "bidirectional"))
    )
    (net (code "79") (name "unconnected-(U1-TOSC2{slash}PG3-Pad18)") (class "Default")
      (node (ref "U1") (pin "18") (pinfunction "TOSC2/PG3_18") (pintype "bidirectional"))
    )
    (net (code "80") (name "unconnected-(U2-NC-Pad6)") (class "Default")
      (node (ref "U2") (pin "6") (pinfunction "NC_6") (pintype "passive"))
    )
    (net (code "81") (name "unconnected-(U2-NC-Pad9)") (class "Default")
      (node (ref "U2") (pin "9") (pinfunction "NC_9") (pintype "passive"))
    )
    (net (code "82") (name "unconnected-(U3-CTS#-Pad9)") (class "Default")
      (node (ref "U3") (pin "9") (pinfunction "CTS#_9") (pintype "passive"))
    )
    (net (code "83") (name "unconnected-(U3-DCD#-Pad12)") (class "Default")
      (node (ref "U3") (pin "12") (pinfunction "DCD#_12") (pintype "passive"))
    )
    (net (code "84") (name "unconnected-(U3-DSR#-Pad10)") (class "Default")
      (node (ref "U3") (pin "10") (pinfunction "DSR#_10") (pintype "passive"))
    )
    (net (code "85") (name "unconnected-(U3-R232-Pad15)") (class "Default")
      (node (ref "U3") (pin "15") (pinfunction "R232_15") (pintype "passive"))
    )
    (net (code "86") (name "unconnected-(U3-RI#-Pad11)") (class "Default")
      (node (ref "U3") (pin "11") (pinfunction "RI#_11") (pintype "passive"))
    )
    (net (code "87") (name "unconnected-(U3-RTS#-Pad14)") (class "Default")
      (node (ref "U3") (pin "14") (pinfunction "RTS#_14") (pintype "passive"))
    )
    (net (code "88") (name "unconnected-(U4-32KHZ-Pad1)") (class "Default")
      (node (ref "U4") (pin "1") (pinfunction "32KHZ_1") (pintype "passive"))
    )
    (net (code "89") (name "unconnected-(U6-GPIO0-Pad12)") (class "Default")
      (node (ref "U6") (pin "12") (pinfunction "GPIO0_12") (pintype "bidirectional"))
    )
    (net (code "90") (name "unconnected-(U6-GPIO02-Pad11)") (class "Default")
      (node (ref "U6") (pin "11") (pinfunction "GPIO02_11") (pintype "bidirectional"))
    )
    (net (code "91") (name "unconnected-(U6-GPIO04-Pad14)") (class "Default")
      (node (ref "U6") (pin "14") (pinfunction "GPIO04_14") (pintype "bidirectional"))
    )
    (net (code "92") (name "unconnected-(U6-GPIO05-Pad13)") (class "Default")
      (node (ref "U6") (pin "13") (pinfunction "GPIO05_13") (pintype "bidirectional"))
    )
    (net (code "93") (name "unconnected-(U6-GPIO12-Pad6)") (class "Default")
      (node (ref "U6") (pin "6") (pinfunction "GPIO12_6") (pintype "bidirectional"))
    )
    (net (code "94") (name "unconnected-(U6-GPIO13-Pad7)") (class "Default")
      (node (ref "U6") (pin "7") (pinfunction "GPIO13_7") (pintype "bidirectional"))
    )
    (net (code "95") (name "unconnected-(U6-GPIO14-Pad5)") (class "Default")
      (node (ref "U6") (pin "5") (pinfunction "GPIO14_5") (pintype "bidirectional"))
    )
    (net (code "96") (name "unconnected-(U6-GPIO15-Pad10)") (class "Default")
      (node (ref "U6") (pin "10") (pinfunction "GPIO15_10") (pintype "bidirectional"))
    )
    (net (code "97") (name "unconnected-(U6-GPIO16-Pad4)") (class "Default")
      (node (ref "U6") (pin "4") (pinfunction "GPIO16_4") (pintype "bidirectional"))
    )
  )
)
